# sha2017_rev0_1_dev.net
KiCad netlist of a schematic drawn in EAGLE
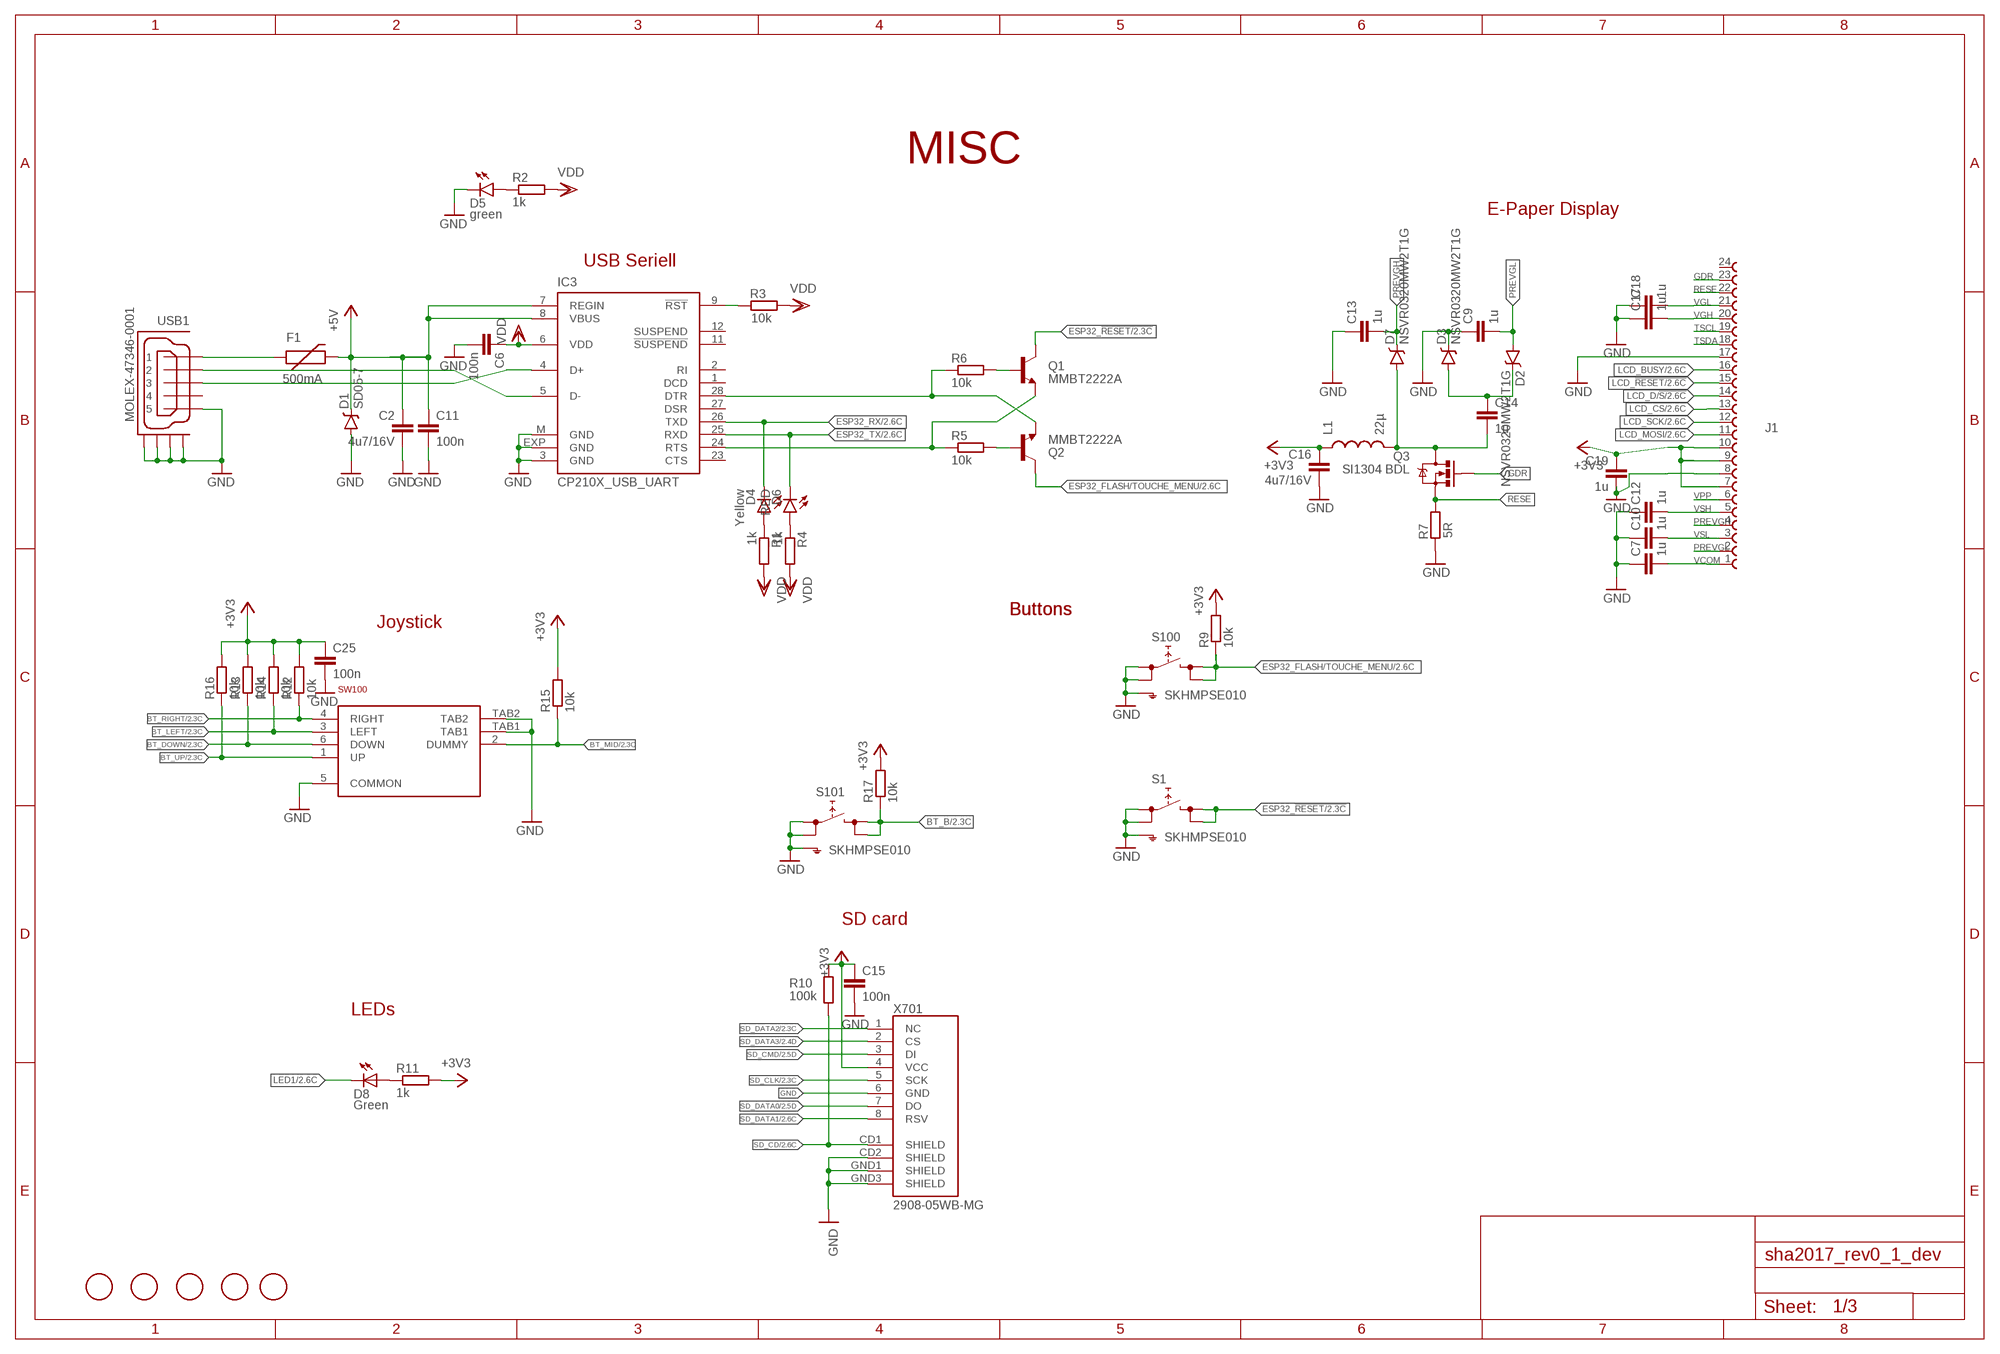
[diagram p0: schematic, sheet 1]
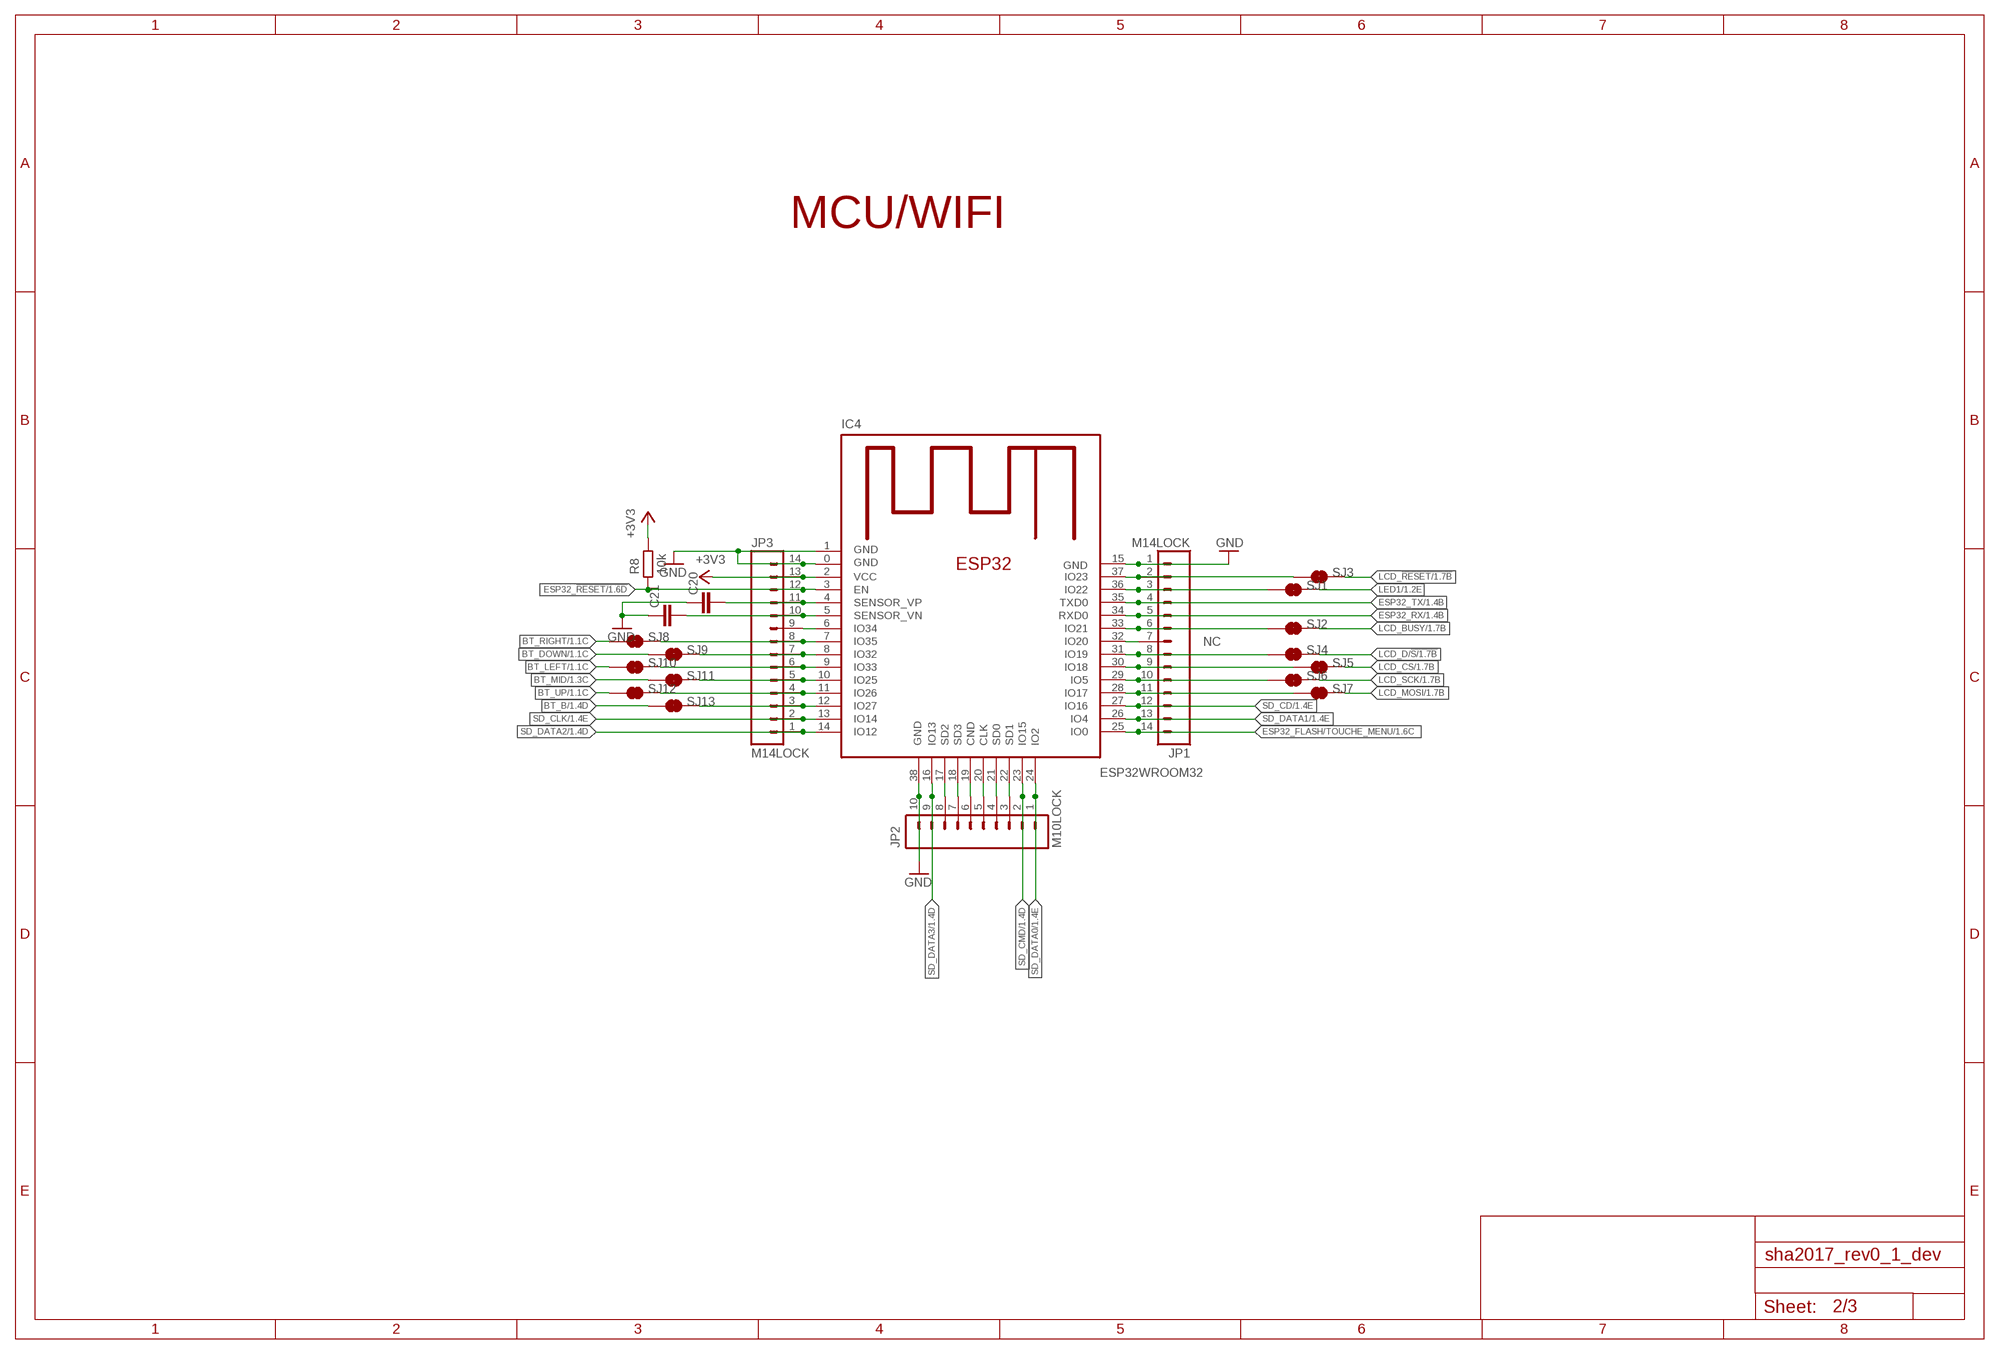
[diagram p1: schematic, sheet 2]
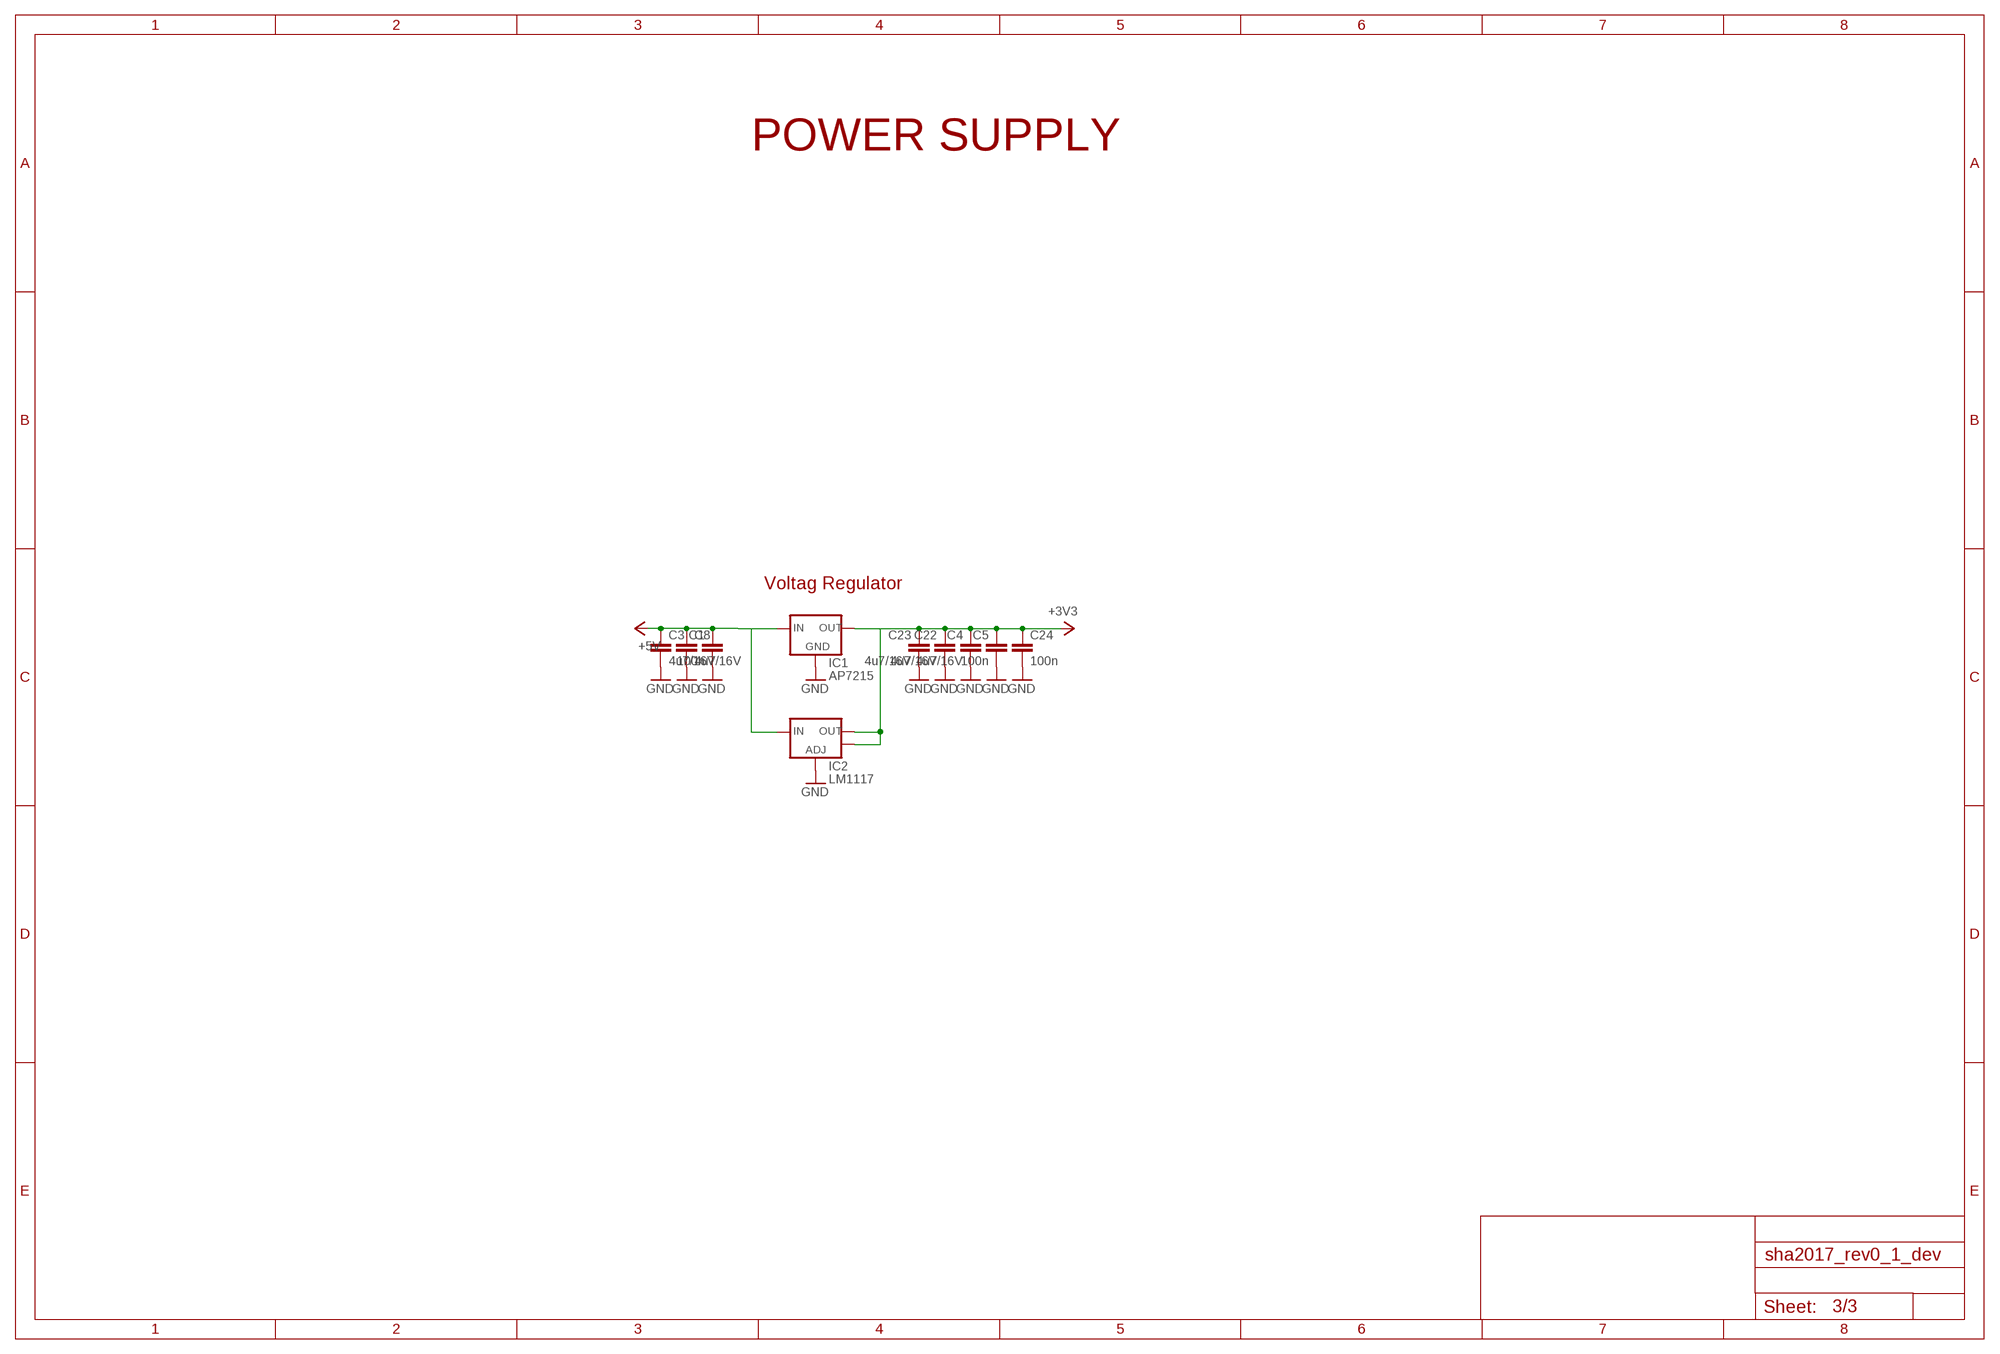
[diagram p2: schematic, sheet 3]

(export (version "E")
  (design (tool "Eeschema 10.0.6"))
  (components
    (comp (ref "C2")
      (value "4u7/16V")
      (footprint "eagle-import:C0805")
      (fields (field (name "PARTNO") "GRM21BR61C475KA88K"))
      (libsource (lib "eagle-import") (part "C-EUC0805"))
    )
    (comp (ref "C6")
      (value "100n")
      (footprint "eagle-import:C0603")
      (fields (field (name "PARTNO") "GRM188R71H104KA93D"))
      (libsource (lib "eagle-import") (part "C-EUC0603"))
    )
    (comp (ref "C7")
      (value "1u")
      (footprint "eagle-import:C0603")
      (fields (field (name "PARTNO") "GRM188R61E105KA12D"))
      (libsource (lib "eagle-import") (part "C-EUC0603"))
    )
    (comp (ref "C9")
      (value "1u")
      (footprint "eagle-import:C0603")
      (fields (field (name "PARTNO") "GRM188R61E105KA12D"))
      (libsource (lib "eagle-import") (part "C-EUC0603"))
    )
    (comp (ref "C10")
      (value "1u")
      (footprint "eagle-import:C0603")
      (fields (field (name "PARTNO") "GRM188R61E105KA12D"))
      (libsource (lib "eagle-import") (part "C-EUC0603"))
    )
    (comp (ref "C11")
      (value "100n")
      (footprint "eagle-import:C0603")
      (fields (field (name "PARTNO") "GRM188R71H104KA93D"))
      (libsource (lib "eagle-import") (part "C-EUC0603"))
    )
    (comp (ref "C12")
      (value "1u")
      (footprint "eagle-import:C0603")
      (fields (field (name "PARTNO") "GRM188R61E105KA12D"))
      (libsource (lib "eagle-import") (part "C-EUC0603"))
    )
    (comp (ref "C13")
      (value "1u")
      (footprint "eagle-import:C0603")
      (fields (field (name "PARTNO") "GRM188R61E105KA12D"))
      (libsource (lib "eagle-import") (part "C-EUC0603"))
    )
    (comp (ref "C14")
      (value "1u")
      (footprint "eagle-import:C0603")
      (fields (field (name "PARTNO") "GRM188R61E105KA12D"))
      (libsource (lib "eagle-import") (part "C-EUC0603"))
    )
    (comp (ref "C15")
      (value "100n")
      (footprint "eagle-import:C0603")
      (fields (field (name "PARTNO") "GRM188R71H104KA93D"))
      (libsource (lib "eagle-import") (part "C-EUC0603"))
    )
    (comp (ref "C16")
      (value "4u7/16V")
      (footprint "eagle-import:C0805")
      (fields (field (name "PARTNO") "GRM21BR61C475KA88K"))
      (libsource (lib "eagle-import") (part "C-EUC0805"))
    )
    (comp (ref "C17")
      (value "1u")
      (footprint "eagle-import:C0603")
      (fields (field (name "PARTNO") "GRM188R61E105KA12D"))
      (libsource (lib "eagle-import") (part "C-EUC0603"))
    )
    (comp (ref "C18")
      (value "1u")
      (footprint "eagle-import:C0603")
      (fields (field (name "PARTNO") "GRM188R61E105KA12D"))
      (libsource (lib "eagle-import") (part "C-EUC0603"))
    )
    (comp (ref "C19")
      (value "1u")
      (footprint "eagle-import:C0603")
      (fields (field (name "PARTNO") "GRM188R61E105KA12D"))
      (libsource (lib "eagle-import") (part "C-EUC0603"))
    )
    (comp (ref "C25")
      (value "100n")
      (footprint "eagle-import:C0603")
      (fields (field (name "PARTNO") "GRM188R71H104KA93D"))
      (libsource (lib "eagle-import") (part "C-EUC0603"))
    )
    (comp (ref "D1")
      (value "SD05-7")
      (footprint "eagle-import:SOD-323")
      (fields (field (name "PARTNO") "PMEG4005EJ,115"))
      (libsource (lib "eagle-import") (part "DIODE-SCHOTTKY-PMEG4005EJ"))
    )
    (comp (ref "D2")
      (value "NSVR0320MW2T1G")
      (footprint "eagle-import:SOD-323")
      (fields (field (name "PARTNO") "BAT20JFILM"))
      (libsource (lib "eagle-import") (part "BAT20JFILM"))
    )
    (comp (ref "D3")
      (value "NSVR0320MW2T1G")
      (footprint "eagle-import:SOD-323")
      (fields (field (name "PARTNO") "BAT20JFILM"))
      (libsource (lib "eagle-import") (part "BAT20JFILM"))
    )
    (comp (ref "D4")
      (value "Yellow")
      (footprint "eagle-import:LED-0603")
      (libsource (lib "eagle-import") (part "LED0603"))
    )
    (comp (ref "D5")
      (value "green")
      (footprint "eagle-import:LED-0603")
      (libsource (lib "eagle-import") (part "LED0603"))
    )
    (comp (ref "D6")
      (value "RED")
      (footprint "eagle-import:LED-0603")
      (libsource (lib "eagle-import") (part "LED0603"))
    )
    (comp (ref "D7")
      (value "NSVR0320MW2T1G")
      (footprint "eagle-import:SOD-323")
      (fields (field (name "PARTNO") "BAT20JFILM"))
      (libsource (lib "eagle-import") (part "BAT20JFILM"))
    )
    (comp (ref "D8")
      (value "Green")
      (footprint "eagle-import:SML1206")
      (fields (field (name "PARTNO") "156120VS75300"))
      (libsource (lib "eagle-import") (part "LEDSML1206"))
    )
    (comp (ref "F1")
      (value "500mA")
      (footprint "eagle-import:PTC-1206")
      (fields (field (name "PARTNO") "0ZCJ0025FF2E"))
      (libsource (lib "eagle-import") (part "PTCSMD"))
    )
    (comp (ref "FD1")
      (value "FIDUCIAL")
      (footprint "eagle-import:FIDUCIAL_1MM")
      (libsource (lib "eagle-import") (part "FIDUCIAL"))
    )
    (comp (ref "FD2")
      (value "FIDUCIAL")
      (footprint "eagle-import:FIDUCIAL_1MM")
      (libsource (lib "eagle-import") (part "FIDUCIAL"))
    )
    (comp (ref "FD3")
      (value "FIDUCIAL")
      (footprint "eagle-import:FIDUCIAL_1MM")
      (libsource (lib "eagle-import") (part "FIDUCIAL"))
    )
    (comp (ref "FD4")
      (value "FIDUCIAL")
      (footprint "eagle-import:FIDUCIAL_1MM")
      (libsource (lib "eagle-import") (part "FIDUCIAL"))
    )
    (comp (ref "FD5")
      (value "FIDUCIAL")
      (footprint "eagle-import:FIDUCIAL_1MM")
      (libsource (lib "eagle-import") (part "FIDUCIAL"))
    )
    (comp (ref "IC3")
      (value "CP210X_USB_UART")
      (footprint "eagle-import:MLP28")
      (fields (field (name "PARTNO") "CP2102-GMR"))
      (libsource (lib "eagle-import") (part "CP210X_USB_UART"))
    )
    (comp (ref "J1")
      (value "68712414022")
      (footprint "eagle-import:68712414022")
      (libsource (lib "eagle-import") (part "68712414022"))
    )
    (comp (ref "L1")
      (value "22µ")
      (footprint "eagle-import:1210")
      (fields (field (name "PARTNO") "NLCV32T-220K-EF"))
      (libsource (lib "eagle-import") (part "INDUCTOR1210"))
    )
    (comp (ref "Q1")
      (value "MMBT2222A")
      (footprint "eagle-import:SOT23-3")
      (fields (field (name "PARTNO") "BC817-25,215"))
      (libsource (lib "eagle-import") (part "TRANSISTOR_NPNMMBT2222A"))
    )
    (comp (ref "Q2")
      (value "MMBT2222A")
      (footprint "eagle-import:SOT23-3")
      (fields (field (name "PARTNO") "BC817-25,215"))
      (libsource (lib "eagle-import") (part "TRANSISTOR_NPNMMBT2222A"))
    )
    (comp (ref "Q3")
      (value "SI1304 BDL")
      (footprint "eagle-import:SOT323")
      (fields (field (name "PARTNO") "SI1308EDL-T1-GE3"))
      (libsource (lib "eagle-import") (part "MOSFET-NCHANNEL2N7002PW"))
    )
    (comp (ref "R1")
      (value "1k")
      (footprint "eagle-import:R0603")
      (fields (field (name "PARTNO") "ERJ-3GEYJ102V"))
      (libsource (lib "eagle-import") (part "R-EU_R0603"))
    )
    (comp (ref "R2")
      (value "1k")
      (footprint "eagle-import:R0603")
      (fields (field (name "PARTNO") "ERJ-3GEYJ102V"))
      (libsource (lib "eagle-import") (part "R-EU_R0603"))
    )
    (comp (ref "R3")
      (value "10k")
      (footprint "eagle-import:R0603")
      (fields (field (name "PARTNO") "ERJ-3GEYJ103V"))
      (libsource (lib "eagle-import") (part "R-EU_R0603"))
    )
    (comp (ref "R4")
      (value "1k")
      (footprint "eagle-import:R0603")
      (fields (field (name "PARTNO") "ERJ-3GEYJ102V"))
      (libsource (lib "eagle-import") (part "R-EU_R0603"))
    )
    (comp (ref "R5")
      (value "10k")
      (footprint "eagle-import:R0603")
      (fields (field (name "PARTNO") "ERJ-3GEYJ103V"))
      (libsource (lib "eagle-import") (part "R-EU_R0603"))
    )
    (comp (ref "R6")
      (value "10k")
      (footprint "eagle-import:R0603")
      (fields (field (name "PARTNO") "ERJ-3GEYJ103V"))
      (libsource (lib "eagle-import") (part "R-EU_R0603"))
    )
    (comp (ref "R7")
      (value "5R")
      (footprint "eagle-import:R0603-DASHES")
      (fields (field (name "PARTNO") "ERJ-3GEYJ5R1V"))
      (libsource (lib "eagle-import") (part "R0603-DASHES"))
    )
    (comp (ref "R9")
      (value "10k")
      (footprint "eagle-import:R0603")
      (fields (field (name "PARTNO") "ERJ-3GEYJ103V"))
      (libsource (lib "eagle-import") (part "R-EU_R0603"))
    )
    (comp (ref "R10")
      (value "100k")
      (footprint "eagle-import:R0603")
      (fields (field (name "PARTNO") "CRCW0603100KFKEA"))
      (libsource (lib "eagle-import") (part "R-EU_R0603"))
    )
    (comp (ref "R11")
      (value "1k")
      (footprint "eagle-import:R0603")
      (fields (field (name "PARTNO") "ERJ-3GEYJ102V"))
      (libsource (lib "eagle-import") (part "R-EU_R0603"))
    )
    (comp (ref "R12")
      (value "10k")
      (footprint "eagle-import:R0603")
      (fields (field (name "PARTNO") "ERJ-3GEYJ103V"))
      (libsource (lib "eagle-import") (part "R-EU_R0603"))
    )
    (comp (ref "R13")
      (value "10k")
      (footprint "eagle-import:R0603")
      (fields (field (name "PARTNO") "ERJ-3GEYJ103V"))
      (libsource (lib "eagle-import") (part "R-EU_R0603"))
    )
    (comp (ref "R14")
      (value "10k")
      (footprint "eagle-import:R0603")
      (fields (field (name "PARTNO") "ERJ-3GEYJ103V"))
      (libsource (lib "eagle-import") (part "R-EU_R0603"))
    )
    (comp (ref "R15")
      (value "10k")
      (footprint "eagle-import:R0603")
      (fields (field (name "PARTNO") "ERJ-3GEYJ103V"))
      (libsource (lib "eagle-import") (part "R-EU_R0603"))
    )
    (comp (ref "R16")
      (value "10k")
      (footprint "eagle-import:R0603")
      (fields (field (name "PARTNO") "ERJ-3GEYJ103V"))
      (libsource (lib "eagle-import") (part "R-EU_R0603"))
    )
    (comp (ref "R17")
      (value "10k")
      (footprint "eagle-import:R0603")
      (fields (field (name "PARTNO") "ERJ-3GEYJ103V"))
      (libsource (lib "eagle-import") (part "R-EU_R0603"))
    )
    (comp (ref "S1")
      (value "SKHMPSE010")
      (footprint "eagle-import:SKHMPXE010")
      (fields (field (name "PARTNO") "SKHMQME010"))
      (libsource (lib "eagle-import") (part "SKHMPE010S"))
    )
    (comp (ref "S100")
      (value "SKHMPSE010")
      (footprint "eagle-import:SKHMPXE010")
      (fields (field (name "PARTNO") "SKHMQME010"))
      (libsource (lib "eagle-import") (part "SKHMPE010S"))
    )
    (comp (ref "S101")
      (value "SKHMPSE010")
      (footprint "eagle-import:SKHMPXE010")
      (fields (field (name "PARTNO") "SKHMQME010"))
      (libsource (lib "eagle-import") (part "SKHMPE010S"))
    )
    (comp (ref "SW100")
      (value "MCMT5-F-V")
      (footprint "eagle-import:MCMT5-F-V")
      (fields (field (name "PARTNO") "SKRHAAE010"))
      (libsource (lib "eagle-import") (part "MCMT5-F-V"))
    )
    (comp (ref "USB1")
      (value "MOLEX-47346-0001")
      (footprint "eagle-import:MOLEX-47364-0001")
      (fields (field (name "PARTNO") "10118194-0001LF"))
      (libsource (lib "eagle-import") (part "MOLEX-47346-0001"))
    )
    (comp (ref "X701")
      (value "2908-05WB-MG")
      (footprint "eagle-import:MICRO-SD-SOCKET-PP")
      (libsource (lib "eagle-import") (part "2908-05WB-MG"))
    )
    (comp (ref "C1")
      (value "100n")
      (footprint "eagle-import:C0603")
      (fields (field (name "PARTNO") "GRM188R71H104KA93D"))
      (libsource (lib "eagle-import") (part "C-EUC0603"))
    )
    (comp (ref "C3")
      (value "4u7/16V")
      (footprint "eagle-import:C0805")
      (fields (field (name "PARTNO") "GRM21BR61C475KA88K"))
      (libsource (lib "eagle-import") (part "C-EUC0805"))
    )
    (comp (ref "C4")
      (value "4u7/16V")
      (footprint "eagle-import:C0805")
      (fields (field (name "PARTNO") "GRM21BR61C475KA88K"))
      (libsource (lib "eagle-import") (part "C-EUC0805"))
    )
    (comp (ref "C5")
      (value "100n")
      (footprint "eagle-import:C0603")
      (fields (field (name "PARTNO") "GRM188R71H104KA93D"))
      (libsource (lib "eagle-import") (part "C-EUC0603"))
    )
    (comp (ref "C8")
      (value "4u7/16V")
      (footprint "eagle-import:C0805")
      (fields (field (name "PARTNO") "GRM21BR61C475KA88K"))
      (libsource (lib "eagle-import") (part "C-EUC0805"))
    )
    (comp (ref "C22")
      (value "4u7/16V")
      (footprint "eagle-import:C0805")
      (fields (field (name "PARTNO") "GRM21BR61C475KA88K"))
      (libsource (lib "eagle-import") (part "C-EUC0805"))
    )
    (comp (ref "C23")
      (value "4u7/16V")
      (footprint "eagle-import:C0805")
      (fields (field (name "PARTNO") "GRM21BR61C475KA88K"))
      (libsource (lib "eagle-import") (part "C-EUC0805"))
    )
    (comp (ref "C24")
      (value "100n")
      (footprint "eagle-import:C0603")
      (fields (field (name "PARTNO") "GRM188R71H104KA93D"))
      (libsource (lib "eagle-import") (part "C-EUC0603"))
    )
    (comp (ref "IC1")
      (value "AP7215")
      (footprint "eagle-import:SOT89")
      (fields (field (name "PARTNO") "AP7215-33YG-13"))
      (libsource (lib "eagle-import") (part "AP7215"))
    )
    (comp (ref "IC2")
      (value "LM1117")
      (footprint "eagle-import:SOT223")
      (fields (field (name "PARTNO") "LM1117MPX-3.3/NOPB"))
      (libsource (lib "eagle-import") (part "V_REG_LM1117SOT223"))
    )
    (comp (ref "C20")
      (value "C-EUC0603")
      (footprint "eagle-import:C0603")
      (libsource (lib "eagle-import") (part "C-EUC0603"))
    )
    (comp (ref "C21")
      (value "C-EUC0603")
      (footprint "eagle-import:C0603")
      (libsource (lib "eagle-import") (part "C-EUC0603"))
    )
    (comp (ref "IC4")
      (value "ESP32WROOM32")
      (footprint "eagle-import:ESP32MOD")
      (libsource (lib "eagle-import") (part "ESP32WROOM32"))
    )
    (comp (ref "JP1")
      (value "M14LOCK")
      (footprint "eagle-import:1X14_LOCK")
      (libsource (lib "eagle-import") (part "M14LOCK"))
    )
    (comp (ref "JP2")
      (value "M10LOCK")
      (footprint "eagle-import:1X10_LOCK")
      (libsource (lib "eagle-import") (part "M10LOCK"))
    )
    (comp (ref "JP3")
      (value "M14LOCK")
      (footprint "eagle-import:1X14_LOCK")
      (libsource (lib "eagle-import") (part "M14LOCK"))
    )
    (comp (ref "R8")
      (value "10k")
      (footprint "eagle-import:R0603")
      (fields (field (name "PARTNO") "ERJ-3GEYJ103V"))
      (libsource (lib "eagle-import") (part "R-EU_R0603"))
    )
    (comp (ref "SJ1")
      (value "JUMPER-PAD-2-NC_BY_TRACE")
      (footprint "eagle-import:PAD-JUMPER-2-NC_BY_TRACE_YES_SILK")
      (libsource (lib "eagle-import") (part "JUMPER-PAD-2-NC_BY_TRACE"))
    )
    (comp (ref "SJ2")
      (value "JUMPER-PAD-2-NC_BY_TRACE")
      (footprint "eagle-import:PAD-JUMPER-2-NC_BY_TRACE_YES_SILK")
      (libsource (lib "eagle-import") (part "JUMPER-PAD-2-NC_BY_TRACE"))
    )
    (comp (ref "SJ3")
      (value "JUMPER-PAD-2-NC_BY_TRACE")
      (footprint "eagle-import:PAD-JUMPER-2-NC_BY_TRACE_YES_SILK")
      (libsource (lib "eagle-import") (part "JUMPER-PAD-2-NC_BY_TRACE"))
    )
    (comp (ref "SJ4")
      (value "JUMPER-PAD-2-NC_BY_TRACE")
      (footprint "eagle-import:PAD-JUMPER-2-NC_BY_TRACE_YES_SILK")
      (libsource (lib "eagle-import") (part "JUMPER-PAD-2-NC_BY_TRACE"))
    )
    (comp (ref "SJ5")
      (value "JUMPER-PAD-2-NC_BY_TRACE")
      (footprint "eagle-import:PAD-JUMPER-2-NC_BY_TRACE_YES_SILK")
      (libsource (lib "eagle-import") (part "JUMPER-PAD-2-NC_BY_TRACE"))
    )
    (comp (ref "SJ6")
      (value "JUMPER-PAD-2-NC_BY_TRACE")
      (footprint "eagle-import:PAD-JUMPER-2-NC_BY_TRACE_YES_SILK")
      (libsource (lib "eagle-import") (part "JUMPER-PAD-2-NC_BY_TRACE"))
    )
    (comp (ref "SJ7")
      (value "JUMPER-PAD-2-NC_BY_TRACE")
      (footprint "eagle-import:PAD-JUMPER-2-NC_BY_TRACE_YES_SILK")
      (libsource (lib "eagle-import") (part "JUMPER-PAD-2-NC_BY_TRACE"))
    )
    (comp (ref "SJ8")
      (value "JUMPER-PAD-2-NC_BY_TRACE")
      (footprint "eagle-import:PAD-JUMPER-2-NC_BY_TRACE_YES_SILK")
      (libsource (lib "eagle-import") (part "JUMPER-PAD-2-NC_BY_TRACE"))
    )
    (comp (ref "SJ9")
      (value "JUMPER-PAD-2-NC_BY_TRACE")
      (footprint "eagle-import:PAD-JUMPER-2-NC_BY_TRACE_YES_SILK")
      (libsource (lib "eagle-import") (part "JUMPER-PAD-2-NC_BY_TRACE"))
    )
    (comp (ref "SJ10")
      (value "JUMPER-PAD-2-NC_BY_TRACE")
      (footprint "eagle-import:PAD-JUMPER-2-NC_BY_TRACE_YES_SILK")
      (libsource (lib "eagle-import") (part "JUMPER-PAD-2-NC_BY_TRACE"))
    )
    (comp (ref "SJ11")
      (value "JUMPER-PAD-2-NC_BY_TRACE")
      (footprint "eagle-import:PAD-JUMPER-2-NC_BY_TRACE_YES_SILK")
      (libsource (lib "eagle-import") (part "JUMPER-PAD-2-NC_BY_TRACE"))
    )
    (comp (ref "SJ12")
      (value "JUMPER-PAD-2-NC_BY_TRACE")
      (footprint "eagle-import:PAD-JUMPER-2-NC_BY_TRACE_YES_SILK")
      (libsource (lib "eagle-import") (part "JUMPER-PAD-2-NC_BY_TRACE"))
    )
    (comp (ref "SJ13")
      (value "JUMPER-PAD-2-NC_BY_TRACE")
      (footprint "eagle-import:PAD-JUMPER-2-NC_BY_TRACE_YES_SILK")
      (libsource (lib "eagle-import") (part "JUMPER-PAD-2-NC_BY_TRACE"))
    )
  )
  (nets
    (net (code "1") (name "+3V3") (class "Default")
      (node (ref "C15") (pin "1") (pinfunction "1_1") (pintype "passive"))
      (node (ref "C16") (pin "1") (pinfunction "1_1") (pintype "passive"))
      (node (ref "C19") (pin "1") (pinfunction "1_1") (pintype "passive"))
      (node (ref "C22") (pin "1") (pinfunction "1_1") (pintype "passive"))
      (node (ref "C23") (pin "1") (pinfunction "1_1") (pintype "passive"))
      (node (ref "C24") (pin "1") (pinfunction "1_1") (pintype "passive"))
      (node (ref "C25") (pin "1") (pinfunction "1_1") (pintype "passive"))
      (node (ref "C4") (pin "1") (pinfunction "1_1") (pintype "passive"))
      (node (ref "C5") (pin "1") (pinfunction "1_1") (pintype "passive"))
      (node (ref "IC1") (pin "3") (pinfunction "OUT_3") (pintype "passive"))
      (node (ref "IC2") (pin "2") (pinfunction "OUT_2") (pintype "output"))
      (node (ref "IC2") (pin "4") (pinfunction "OUT_4") (pintype "output"))
      (node (ref "IC4") (pin "2") (pinfunction "VCC_2") (pintype "power_in"))
      (node (ref "J1") (pin "10") (pinfunction "10_10") (pintype "passive"))
      (node (ref "J1") (pin "7") (pinfunction "7_7") (pintype "passive"))
      (node (ref "J1") (pin "9") (pinfunction "9_9") (pintype "passive"))
      (node (ref "JP3") (pin "13") (pinfunction "13_13") (pintype "passive"))
      (node (ref "L1") (pin "1") (pinfunction "1_1") (pintype "passive"))
      (node (ref "R10") (pin "1") (pinfunction "1_1") (pintype "passive"))
      (node (ref "R11") (pin "2") (pinfunction "2_2") (pintype "passive"))
      (node (ref "R12") (pin "2") (pinfunction "2_2") (pintype "passive"))
      (node (ref "R13") (pin "2") (pinfunction "2_2") (pintype "passive"))
      (node (ref "R14") (pin "2") (pinfunction "2_2") (pintype "passive"))
      (node (ref "R15") (pin "2") (pinfunction "2_2") (pintype "passive"))
      (node (ref "R16") (pin "2") (pinfunction "2_2") (pintype "passive"))
      (node (ref "R17") (pin "2") (pinfunction "2_2") (pintype "passive"))
      (node (ref "R8") (pin "1") (pinfunction "1_1") (pintype "passive"))
      (node (ref "R9") (pin "2") (pinfunction "2_2") (pintype "passive"))
      (node (ref "X701") (pin "4") (pinfunction "VCC_4") (pintype "bidirectional"))
    )
    (net (code "2") (name "+5V") (class "Default")
      (node (ref "C1") (pin "1") (pinfunction "1_1") (pintype "passive"))
      (node (ref "C11") (pin "1") (pinfunction "1_1") (pintype "passive"))
      (node (ref "C2") (pin "1") (pinfunction "1_1") (pintype "passive"))
      (node (ref "C3") (pin "1") (pinfunction "1_1") (pintype "passive"))
      (node (ref "C8") (pin "1") (pinfunction "1_1") (pintype "passive"))
      (node (ref "D1") (pin "C") (pinfunction "C_C") (pintype "passive"))
      (node (ref "F1") (pin "2") (pinfunction "2_2") (pintype "bidirectional"))
      (node (ref "IC1") (pin "2") (pinfunction "IN_2") (pintype "input"))
      (node (ref "IC1") (pin "2@") (pinfunction "IN_2@") (pintype "input"))
      (node (ref "IC2") (pin "3") (pinfunction "IN_3") (pintype "input"))
      (node (ref "IC3") (pin "7") (pinfunction "REGIN_7") (pintype "passive"))
      (node (ref "IC3") (pin "8") (pinfunction "VBUS_8") (pintype "input"))
    )
    (net (code "3") (name "BT_B") (class "Default")
      (node (ref "R17") (pin "1") (pinfunction "1_1") (pintype "passive"))
      (node (ref "S101") (pin "3") (pinfunction "2.1_3") (pintype "passive"))
      (node (ref "S101") (pin "4") (pinfunction "2.2_4") (pintype "passive"))
      (node (ref "SJ13") (pin "1") (pinfunction "1_1") (pintype "passive"))
    )
    (net (code "4") (name "BT_DOWN") (class "Default")
      (node (ref "R13") (pin "1") (pinfunction "1_1") (pintype "passive"))
      (node (ref "SJ9") (pin "1") (pinfunction "1_1") (pintype "passive"))
      (node (ref "SW100") (pin "6") (pinfunction "DOWN_6") (pintype "bidirectional"))
    )
    (net (code "5") (name "BT_LEFT") (class "Default")
      (node (ref "R14") (pin "1") (pinfunction "1_1") (pintype "passive"))
      (node (ref "SJ10") (pin "1") (pinfunction "1_1") (pintype "passive"))
      (node (ref "SW100") (pin "3") (pinfunction "LEFT_3") (pintype "bidirectional"))
    )
    (net (code "6") (name "BT_MID") (class "Default")
      (node (ref "R15") (pin "1") (pinfunction "1_1") (pintype "passive"))
      (node (ref "SJ11") (pin "1") (pinfunction "1_1") (pintype "passive"))
      (node (ref "SW100") (pin "2") (pinfunction "DUMMY_2") (pintype "bidirectional"))
    )
    (net (code "7") (name "BT_RIGHT") (class "Default")
      (node (ref "R12") (pin "1") (pinfunction "1_1") (pintype "passive"))
      (node (ref "SJ8") (pin "1") (pinfunction "1_1") (pintype "passive"))
      (node (ref "SW100") (pin "4") (pinfunction "RIGHT_4") (pintype "bidirectional"))
    )
    (net (code "8") (name "BT_UP") (class "Default")
      (node (ref "R16") (pin "1") (pinfunction "1_1") (pintype "passive"))
      (node (ref "SJ12") (pin "1") (pinfunction "1_1") (pintype "passive"))
      (node (ref "SW100") (pin "1") (pinfunction "UP_1") (pintype "bidirectional"))
    )
    (net (code "9") (name "ESP32_FLASH{slash}TOUCHE_MENU") (class "Default")
      (node (ref "IC4") (pin "25") (pinfunction "IO0_25") (pintype "bidirectional"))
      (node (ref "JP1") (pin "14") (pinfunction "14_14") (pintype "passive"))
      (node (ref "Q2") (pin "3") (pinfunction "C_3") (pintype "passive"))
      (node (ref "R9") (pin "1") (pinfunction "1_1") (pintype "passive"))
      (node (ref "S100") (pin "3") (pinfunction "2.1_3") (pintype "passive"))
      (node (ref "S100") (pin "4") (pinfunction "2.2_4") (pintype "passive"))
    )
    (net (code "10") (name "ESP32_RX") (class "Default")
      (node (ref "D4") (pin "C") (pinfunction "C_C") (pintype "passive"))
      (node (ref "IC3") (pin "26") (pinfunction "TXD_26") (pintype "output"))
      (node (ref "IC4") (pin "34") (pinfunction "RXD0_34") (pintype "bidirectional"))
      (node (ref "JP1") (pin "5") (pinfunction "5_5") (pintype "passive"))
    )
    (net (code "11") (name "ESP32_TX") (class "Default")
      (node (ref "D6") (pin "C") (pinfunction "C_C") (pintype "passive"))
      (node (ref "IC3") (pin "25") (pinfunction "RXD_25") (pintype "input"))
      (node (ref "IC4") (pin "35") (pinfunction "TXD0_35") (pintype "bidirectional"))
      (node (ref "JP1") (pin "4") (pinfunction "4_4") (pintype "passive"))
    )
    (net (code "12") (name "ESP32_~{RESET}") (class "Default")
      (node (ref "IC4") (pin "3") (pinfunction "EN_3") (pintype "bidirectional"))
      (node (ref "JP3") (pin "12") (pinfunction "12_12") (pintype "passive"))
      (node (ref "Q1") (pin "3") (pinfunction "C_3") (pintype "passive"))
      (node (ref "R8") (pin "2") (pinfunction "2_2") (pintype "passive"))
      (node (ref "S1") (pin "3") (pinfunction "2.1_3") (pintype "passive"))
      (node (ref "S1") (pin "4") (pinfunction "2.2_4") (pintype "passive"))
    )
    (net (code "13") (name "GDR") (class "Default")
      (node (ref "J1") (pin "23") (pinfunction "23_23") (pintype "passive"))
      (node (ref "Q3") (pin "1") (pinfunction "G_1") (pintype "passive"))
    )
    (net (code "14") (name "GND") (class "Default")
      (node (ref "C1") (pin "2") (pinfunction "2_2") (pintype "passive"))
      (node (ref "C10") (pin "1") (pinfunction "1_1") (pintype "passive"))
      (node (ref "C11") (pin "2") (pinfunction "2_2") (pintype "passive"))
      (node (ref "C12") (pin "1") (pinfunction "1_1") (pintype "passive"))
      (node (ref "C13") (pin "1") (pinfunction "1_1") (pintype "passive"))
      (node (ref "C15") (pin "2") (pinfunction "2_2") (pintype "passive"))
      (node (ref "C16") (pin "2") (pinfunction "2_2") (pintype "passive"))
      (node (ref "C17") (pin "1") (pinfunction "1_1") (pintype "passive"))
      (node (ref "C18") (pin "1") (pinfunction "1_1") (pintype "passive"))
      (node (ref "C19") (pin "2") (pinfunction "2_2") (pintype "passive"))
      (node (ref "C2") (pin "2") (pinfunction "2_2") (pintype "passive"))
      (node (ref "C20") (pin "1") (pinfunction "1_1") (pintype "passive"))
      (node (ref "C21") (pin "1") (pinfunction "1_1") (pintype "passive"))
      (node (ref "C22") (pin "2") (pinfunction "2_2") (pintype "passive"))
      (node (ref "C23") (pin "2") (pinfunction "2_2") (pintype "passive"))
      (node (ref "C24") (pin "2") (pinfunction "2_2") (pintype "passive"))
      (node (ref "C25") (pin "2") (pinfunction "2_2") (pintype "passive"))
      (node (ref "C3") (pin "2") (pinfunction "2_2") (pintype "passive"))
      (node (ref "C4") (pin "2") (pinfunction "2_2") (pintype "passive"))
      (node (ref "C5") (pin "2") (pinfunction "2_2") (pintype "passive"))
      (node (ref "C6") (pin "2") (pinfunction "2_2") (pintype "passive"))
      (node (ref "C7") (pin "1") (pinfunction "1_1") (pintype "passive"))
      (node (ref "C8") (pin "2") (pinfunction "2_2") (pintype "passive"))
      (node (ref "C9") (pin "1") (pinfunction "1_1") (pintype "passive"))
      (node (ref "D1") (pin "A") (pinfunction "A_A") (pintype "passive"))
      (node (ref "D3") (pin "C") (pinfunction "C_C") (pintype "passive"))
      (node (ref "D5") (pin "C") (pinfunction "C_C") (pintype "passive"))
      (node (ref "IC1") (pin "1") (pinfunction "GND_1") (pintype "input"))
      (node (ref "IC2") (pin "1") (pinfunction "ADJ_1") (pintype "input"))
      (node (ref "IC3") (pin "3") (pinfunction "GND_3") (pintype "power_in"))
      (node (ref "IC3") (pin "EXP") (pinfunction "GND_EXP") (pintype "power_in"))
      (node (ref "IC3") (pin "M") (pinfunction "GND_M") (pintype "power_in"))
      (node (ref "IC4") (pin "0") (pinfunction "GND_0") (pintype "power_in"))
      (node (ref "IC4") (pin "1") (pinfunction "GND_1") (pintype "power_in"))
      (node (ref "IC4") (pin "15") (pinfunction "GND_15") (pintype "power_in"))
      (node (ref "IC4") (pin "38") (pinfunction "GND_38") (pintype "power_in"))
      (node (ref "J1") (pin "17") (pinfunction "17_17") (pintype "passive"))
      (node (ref "J1") (pin "8") (pinfunction "8_8") (pintype "passive"))
      (node (ref "JP1") (pin "1") (pinfunction "1_1") (pintype "passive"))
      (node (ref "JP2") (pin "10") (pinfunction "10_10") (pintype "passive"))
      (node (ref "JP3") (pin "14") (pinfunction "14_14") (pintype "passive"))
      (node (ref "R7") (pin "2") (pinfunction "2_2") (pintype "passive"))
      (node (ref "S1") (pin "1") (pinfunction "1.1_1") (pintype "passive"))
      (node (ref "S1") (pin "2") (pinfunction "1.2_2") (pintype "passive"))
      (node (ref "S1") (pin "5") (pinfunction "SH_5") (pintype "passive"))
      (node (ref "S100") (pin "1") (pinfunction "1.1_1") (pintype "passive"))
      (node (ref "S100") (pin "2") (pinfunction "1.2_2") (pintype "passive"))
      (node (ref "S100") (pin "5") (pinfunction "SH_5") (pintype "passive"))
      (node (ref "S101") (pin "1") (pinfunction "1.1_1") (pintype "passive"))
      (node (ref "S101") (pin "2") (pinfunction "1.2_2") (pintype "passive"))
      (node (ref "S101") (pin "5") (pinfunction "SH_5") (pintype "passive"))
      (node (ref "SW100") (pin "5") (pinfunction "COMMON_5") (pintype "bidirectional"))
      (node (ref "SW100") (pin "TAB1") (pinfunction "TAB1_TAB1") (pintype "bidirectional"))
      (node (ref "SW100") (pin "TAB2") (pinfunction "TAB2_TAB2") (pintype "bidirectional"))
      (node (ref "USB1") (pin "5") (pinfunction "5_5") (pintype "input"))
      (node (ref "USB1") (pin "GND1") (pinfunction "GND1_GND1") (pintype "bidirectional"))
      (node (ref "USB1") (pin "GND2") (pinfunction "GND2_GND2") (pintype "bidirectional"))
      (node (ref "USB1") (pin "GND3") (pinfunction "GND3_GND3") (pintype "bidirectional"))
      (node (ref "USB1") (pin "GND4") (pinfunction "GND4_GND4") (pintype "bidirectional"))
      (node (ref "X701") (pin "6") (pinfunction "GND_6") (pintype "bidirectional"))
      (node (ref "X701") (pin "CD2") (pinfunction "SHIELD_CD2") (pintype "bidirectional"))
      (node (ref "X701") (pin "GND1") (pinfunction "SHIELD_GND1") (pintype "bidirectional"))
      (node (ref "X701") (pin "GND3") (pinfunction "SHIELD_GND3") (pintype "bidirectional"))
    )
    (net (code "15") (name "LCD_BUSY") (class "Default")
      (node (ref "J1") (pin "16") (pinfunction "16_16") (pintype "passive"))
      (node (ref "SJ2") (pin "2") (pinfunction "2_2") (pintype "passive"))
    )
    (net (code "16") (name "LCD_CS") (class "Default")
      (node (ref "J1") (pin "13") (pinfunction "13_13") (pintype "passive"))
      (node (ref "SJ5") (pin "2") (pinfunction "2_2") (pintype "passive"))
    )
    (net (code "17") (name "LCD_D{slash}~{S}") (class "Default")
      (node (ref "J1") (pin "14") (pinfunction "14_14") (pintype "passive"))
      (node (ref "SJ4") (pin "2") (pinfunction "2_2") (pintype "passive"))
    )
    (net (code "18") (name "LCD_MOSI") (class "Default")
      (node (ref "J1") (pin "11") (pinfunction "11_11") (pintype "passive"))
      (node (ref "SJ7") (pin "2") (pinfunction "2_2") (pintype "passive"))
    )
    (net (code "19") (name "LCD_SCK") (class "Default")
      (node (ref "J1") (pin "12") (pinfunction "12_12") (pintype "passive"))
      (node (ref "SJ6") (pin "2") (pinfunction "2_2") (pintype "passive"))
    )
    (net (code "20") (name "LCD_~{RESET}") (class "Default")
      (node (ref "J1") (pin "15") (pinfunction "15_15") (pintype "passive"))
      (node (ref "SJ3") (pin "2") (pinfunction "2_2") (pintype "passive"))
    )
    (net (code "21") (name "LED1") (class "Default")
      (node (ref "D8") (pin "C") (pinfunction "C_C") (pintype "passive"))
      (node (ref "SJ1") (pin "2") (pinfunction "2_2") (pintype "passive"))
    )
    (net (code "22") (name "Net-(C14-Pad1)") (class "Default")
      (node (ref "C14") (pin "1") (pinfunction "1_1") (pintype "passive"))
      (node (ref "D2") (pin "C") (pinfunction "C_C") (pintype "passive"))
      (node (ref "D3") (pin "A") (pinfunction "A_A") (pintype "passive"))
    )
    (net (code "23") (name "Net-(D4-PadA)") (class "Default")
      (node (ref "D4") (pin "A") (pinfunction "A_A") (pintype "passive"))
      (node (ref "R1") (pin "1") (pinfunction "1_1") (pintype "passive"))
    )
    (net (code "24") (name "Net-(D5-PadA)") (class "Default")
      (node (ref "D5") (pin "A") (pinfunction "A_A") (pintype "passive"))
      (node (ref "R2") (pin "1") (pinfunction "1_1") (pintype "passive"))
    )
    (net (code "25") (name "Net-(D6-PadA)") (class "Default")
      (node (ref "D6") (pin "A") (pinfunction "A_A") (pintype "passive"))
      (node (ref "R4") (pin "1") (pinfunction "1_1") (pintype "passive"))
    )
    (net (code "26") (name "Net-(D8-PadA)") (class "Default")
      (node (ref "D8") (pin "A") (pinfunction "A_A") (pintype "passive"))
      (node (ref "R11") (pin "1") (pinfunction "1_1") (pintype "passive"))
    )
    (net (code "27") (name "Net-(F1-Pad1)") (class "Default")
      (node (ref "F1") (pin "1") (pinfunction "1_1") (pintype "bidirectional"))
      (node (ref "USB1") (pin "1") (pinfunction "1_1") (pintype "input"))
    )
    (net (code "28") (name "Net-(IC3-D+)") (class "Default")
      (node (ref "IC3") (pin "4") (pinfunction "D+_4") (pintype "bidirectional"))
      (node (ref "USB1") (pin "3") (pinfunction "3_3") (pintype "input"))
    )
    (net (code "29") (name "Net-(IC3-D-)") (class "Default")
      (node (ref "IC3") (pin "5") (pinfunction "D-_5") (pintype "bidirectional"))
      (node (ref "USB1") (pin "2") (pinfunction "2_2") (pintype "input"))
    )
    (net (code "30") (name "Net-(IC3-DTR)") (class "Default")
      (node (ref "IC3") (pin "28") (pinfunction "DTR_28") (pintype "output"))
      (node (ref "Q2") (pin "2") (pinfunction "E_2") (pintype "passive"))
      (node (ref "R6") (pin "1") (pinfunction "1_1") (pintype "passive"))
    )
    (net (code "31") (name "Net-(IC3-RTS)") (class "Default")
      (node (ref "IC3") (pin "24") (pinfunction "RTS_24") (pintype "output"))
      (node (ref "Q1") (pin "2") (pinfunction "E_2") (pintype "passive"))
      (node (ref "R5") (pin "1") (pinfunction "1_1") (pintype "passive"))
    )
    (net (code "32") (name "Net-(IC3-~{RST})") (class "Default")
      (node (ref "IC3") (pin "9") (pinfunction "~{RST}_9") (pintype "bidirectional"))
      (node (ref "R3") (pin "2") (pinfunction "2_2") (pintype "passive"))
    )
    (net (code "33") (name "Net-(IC4-CLK)") (class "Default")
      (node (ref "IC4") (pin "20") (pinfunction "CLK_20") (pintype "bidirectional"))
      (node (ref "JP2") (pin "5") (pinfunction "5_5") (pintype "passive"))
    )
    (net (code "34") (name "Net-(IC4-CND)") (class "Default")
      (node (ref "IC4") (pin "19") (pinfunction "CND_19") (pintype "bidirectional"))
      (node (ref "JP2") (pin "6") (pinfunction "6_6") (pintype "passive"))
    )
    (net (code "35") (name "Net-(IC4-IO5)") (class "Default")
      (node (ref "IC4") (pin "29") (pinfunction "IO5_29") (pintype "bidirectional"))
      (node (ref "JP1") (pin "10") (pinfunction "10_10") (pintype "passive"))
      (node (ref "SJ6") (pin "1") (pinfunction "1_1") (pintype "passive"))
    )
    (net (code "36") (name "Net-(IC4-IO17)") (class "Default")
      (node (ref "IC4") (pin "28") (pinfunction "IO17_28") (pintype "bidirectional"))
      (node (ref "JP1") (pin "11") (pinfunction "11_11") (pintype "passive"))
      (node (ref "SJ7") (pin "1") (pinfunction "1_1") (pintype "passive"))
    )
    (net (code "37") (name "Net-(IC4-IO18)") (class "Default")
      (node (ref "IC4") (pin "30") (pinfunction "IO18_30") (pintype "bidirectional"))
      (node (ref "JP1") (pin "9") (pinfunction "9_9") (pintype "passive"))
      (node (ref "SJ5") (pin "1") (pinfunction "1_1") (pintype "passive"))
    )
    (net (code "38") (name "Net-(IC4-IO19)") (class "Default")
      (node (ref "IC4") (pin "31") (pinfunction "IO19_31") (pintype "bidirectional"))
      (node (ref "JP1") (pin "8") (pinfunction "8_8") (pintype "passive"))
      (node (ref "SJ4") (pin "1") (pinfunction "1_1") (pintype "passive"))
    )
    (net (code "39") (name "Net-(IC4-IO20)") (class "Default")
      (node (ref "IC4") (pin "32") (pinfunction "IO20_32") (pintype "bidirectional"))
      (node (ref "JP1") (pin "7") (pinfunction "7_7") (pintype "passive"))
    )
    (net (code "40") (name "Net-(IC4-IO21)") (class "Default")
      (node (ref "IC4") (pin "33") (pinfunction "IO21_33") (pintype "bidirectional"))
      (node (ref "JP1") (pin "6") (pinfunction "6_6") (pintype "passive"))
      (node (ref "SJ2") (pin "1") (pinfunction "1_1") (pintype "passive"))
    )
    (net (code "41") (name "Net-(IC4-IO22)") (class "Default")
      (node (ref "IC4") (pin "36") (pinfunction "IO22_36") (pintype "bidirectional"))
      (node (ref "JP1") (pin "3") (pinfunction "3_3") (pintype "passive"))
      (node (ref "SJ1") (pin "1") (pinfunction "1_1") (pintype "passive"))
    )
    (net (code "42") (name "Net-(IC4-IO23)") (class "Default")
      (node (ref "IC4") (pin "37") (pinfunction "IO23_37") (pintype "bidirectional"))
      (node (ref "JP1") (pin "2") (pinfunction "2_2") (pintype "passive"))
      (node (ref "SJ3") (pin "1") (pinfunction "1_1") (pintype "passive"))
    )
    (net (code "43") (name "Net-(IC4-IO25)") (class "Default")
      (node (ref "IC4") (pin "10") (pinfunction "IO25_10") (pintype "bidirectional"))
      (node (ref "JP3") (pin "5") (pinfunction "5_5") (pintype "passive"))
      (node (ref "SJ11") (pin "2") (pinfunction "2_2") (pintype "passive"))
    )
    (net (code "44") (name "Net-(IC4-IO26)") (class "Default")
      (node (ref "IC4") (pin "11") (pinfunction "IO26_11") (pintype "bidirectional"))
      (node (ref "JP3") (pin "4") (pinfunction "4_4") (pintype "passive"))
      (node (ref "SJ12") (pin "2") (pinfunction "2_2") (pintype "passive"))
    )
    (net (code "45") (name "Net-(IC4-IO27)") (class "Default")
      (node (ref "IC4") (pin "12") (pinfunction "IO27_12") (pintype "bidirectional"))
      (node (ref "JP3") (pin "3") (pinfunction "3_3") (pintype "passive"))
      (node (ref "SJ13") (pin "2") (pinfunction "2_2") (pintype "passive"))
    )
    (net (code "46") (name "Net-(IC4-IO32)") (class "Default")
      (node (ref "IC4") (pin "8") (pinfunction "IO32_8") (pintype "bidirectional"))
      (node (ref "JP3") (pin "7") (pinfunction "7_7") (pintype "passive"))
      (node (ref "SJ9") (pin "2") (pinfunction "2_2") (pintype "passive"))
    )
    (net (code "47") (name "Net-(IC4-IO33)") (class "Default")
      (node (ref "IC4") (pin "9") (pinfunction "IO33_9") (pintype "bidirectional"))
      (node (ref "JP3") (pin "6") (pinfunction "6_6") (pintype "passive"))
      (node (ref "SJ10") (pin "2") (pinfunction "2_2") (pintype "passive"))
    )
    (net (code "48") (name "Net-(IC4-IO34)") (class "Default")
      (node (ref "IC4") (pin "6") (pinfunction "IO34_6") (pintype "bidirectional"))
      (node (ref "JP3") (pin "9") (pinfunction "9_9") (pintype "passive"))
    )
    (net (code "49") (name "Net-(IC4-IO35)") (class "Default")
      (node (ref "IC4") (pin "7") (pinfunction "IO35_7") (pintype "bidirectional"))
      (node (ref "JP3") (pin "8") (pinfunction "8_8") (pintype "passive"))
      (node (ref "SJ8") (pin "2") (pinfunction "2_2") (pintype "passive"))
    )
    (net (code "50") (name "Net-(IC4-SD0)") (class "Default")
      (node (ref "IC4") (pin "21") (pinfunction "SD0_21") (pintype "bidirectional"))
      (node (ref "JP2") (pin "4") (pinfunction "4_4") (pintype "passive"))
    )
    (net (code "51") (name "Net-(IC4-SD1)") (class "Default")
      (node (ref "IC4") (pin "22") (pinfunction "SD1_22") (pintype "bidirectional"))
      (node (ref "JP2") (pin "3") (pinfunction "3_3") (pintype "passive"))
    )
    (net (code "52") (name "Net-(IC4-SD2)") (class "Default")
      (node (ref "IC4") (pin "17") (pinfunction "SD2_17") (pintype "bidirectional"))
      (node (ref "JP2") (pin "8") (pinfunction "8_8") (pintype "passive"))
    )
    (net (code "53") (name "Net-(IC4-SD3)") (class "Default")
      (node (ref "IC4") (pin "18") (pinfunction "SD3_18") (pintype "bidirectional"))
      (node (ref "JP2") (pin "7") (pinfunction "7_7") (pintype "passive"))
    )
    (net (code "54") (name "Net-(IC4-SENSOR_VN)") (class "Default")
      (node (ref "C21") (pin "2") (pinfunction "2_2") (pintype "passive"))
      (node (ref "IC4") (pin "5") (pinfunction "SENSOR_VN_5") (pintype "bidirectional"))
      (node (ref "JP3") (pin "10") (pinfunction "10_10") (pintype "passive"))
    )
    (net (code "55") (name "Net-(IC4-SENSOR_VP)") (class "Default")
      (node (ref "C20") (pin "2") (pinfunction "2_2") (pintype "passive"))
      (node (ref "IC4") (pin "4") (pinfunction "SENSOR_VP_4") (pintype "bidirectional"))
      (node (ref "JP3") (pin "11") (pinfunction "11_11") (pintype "passive"))
    )
    (net (code "56") (name "Net-(Q1-B)") (class "Default")
      (node (ref "Q1") (pin "1") (pinfunction "B_1") (pintype "passive"))
      (node (ref "R6") (pin "2") (pinfunction "2_2") (pintype "passive"))
    )
    (net (code "57") (name "Net-(Q2-B)") (class "Default")
      (node (ref "Q2") (pin "1") (pinfunction "B_1") (pintype "passive"))
      (node (ref "R5") (pin "2") (pinfunction "2_2") (pintype "passive"))
    )
    (net (code "58") (name "Net-(Q3-D)") (class "Default")
      (node (ref "C14") (pin "2") (pinfunction "2_2") (pintype "passive"))
      (node (ref "D7") (pin "A") (pinfunction "A_A") (pintype "passive"))
      (node (ref "L1") (pin "2") (pinfunction "2_2") (pintype "passive"))
      (node (ref "Q3") (pin "3") (pinfunction "D_3") (pintype "passive"))
    )
    (net (code "59") (name "PREVGH") (class "Default")
      (node (ref "C13") (pin "2") (pinfunction "2_2") (pintype "passive"))
      (node (ref "D7") (pin "C") (pinfunction "C_C") (pintype "passive"))
      (node (ref "J1") (pin "4") (pinfunction "4_4") (pintype "passive"))
    )
    (net (code "60") (name "PREVGL") (class "Default")
      (node (ref "C9") (pin "2") (pinfunction "2_2") (pintype "passive"))
      (node (ref "D2") (pin "A") (pinfunction "A_A") (pintype "passive"))
      (node (ref "J1") (pin "2") (pinfunction "2_2") (pintype "passive"))
    )
    (net (code "61") (name "RESE") (class "Default")
      (node (ref "J1") (pin "22") (pinfunction "22_22") (pintype "passive"))
      (node (ref "Q3") (pin "2") (pinfunction "S_2") (pintype "passive"))
      (node (ref "R7") (pin "1") (pinfunction "1_1") (pintype "passive"))
    )
    (net (code "62") (name "SD_CD") (class "Default")
      (node (ref "IC4") (pin "27") (pinfunction "IO16_27") (pintype "bidirectional"))
      (node (ref "JP1") (pin "12") (pinfunction "12_12") (pintype "passive"))
      (node (ref "R10") (pin "2") (pinfunction "2_2") (pintype "passive"))
      (node (ref "X701") (pin "CD1") (pinfunction "SHIELD_CD1") (pintype "bidirectional"))
    )
    (net (code "63") (name "SD_CLK") (class "Default")
      (node (ref "IC4") (pin "13") (pinfunction "IO14_13") (pintype "bidirectional"))
      (node (ref "JP3") (pin "2") (pinfunction "2_2") (pintype "passive"))
      (node (ref "X701") (pin "5") (pinfunction "SCK_5") (pintype "bidirectional"))
    )
    (net (code "64") (name "SD_CMD") (class "Default")
      (node (ref "IC4") (pin "23") (pinfunction "IO15_23") (pintype "bidirectional"))
      (node (ref "JP2") (pin "2") (pinfunction "2_2") (pintype "passive"))
      (node (ref "X701") (pin "3") (pinfunction "DI_3") (pintype "bidirectional"))
    )
    (net (code "65") (name "SD_DATA0") (class "Default")
      (node (ref "IC4") (pin "24") (pinfunction "IO2_24") (pintype "bidirectional"))
      (node (ref "JP2") (pin "1") (pinfunction "1_1") (pintype "passive"))
      (node (ref "X701") (pin "7") (pinfunction "DO_7") (pintype "bidirectional"))
    )
    (net (code "66") (name "SD_DATA1") (class "Default")
      (node (ref "IC4") (pin "26") (pinfunction "IO4_26") (pintype "bidirectional"))
      (node (ref "JP1") (pin "13") (pinfunction "13_13") (pintype "passive"))
      (node (ref "X701") (pin "8") (pinfunction "RSV_8") (pintype "bidirectional"))
    )
    (net (code "67") (name "SD_DATA2") (class "Default")
      (node (ref "IC4") (pin "14") (pinfunction "IO12_14") (pintype "bidirectional"))
      (node (ref "JP3") (pin "1") (pinfunction "1_1") (pintype "passive"))
      (node (ref "X701") (pin "1") (pinfunction "NC_1") (pintype "bidirectional"))
    )
    (net (code "68") (name "SD_DATA3") (class "Default")
      (node (ref "IC4") (pin "16") (pinfunction "IO13_16") (pintype "bidirectional"))
      (node (ref "JP2") (pin "9") (pinfunction "9_9") (pintype "passive"))
      (node (ref "X701") (pin "2") (pinfunction "CS_2") (pintype "bidirectional"))
    )
    (net (code "69") (name "TSCL") (class "Default")
      (node (ref "J1") (pin "19") (pinfunction "19_19") (pintype "passive"))
    )
    (net (code "70") (name "TSDA") (class "Default")
      (node (ref "J1") (pin "18") (pinfunction "18_18") (pintype "passive"))
    )
    (net (code "71") (name "VCOM") (class "Default")
      (node (ref "C7") (pin "2") (pinfunction "2_2") (pintype "passive"))
      (node (ref "J1") (pin "1") (pinfunction "1_1") (pintype "passive"))
    )
    (net (code "72") (name "VDD") (class "Default")
      (node (ref "C6") (pin "1") (pinfunction "1_1") (pintype "passive"))
      (node (ref "IC3") (pin "6") (pinfunction "VDD_6") (pintype "power_in"))
      (node (ref "R1") (pin "2") (pinfunction "2_2") (pintype "passive"))
      (node (ref "R2") (pin "2") (pinfunction "2_2") (pintype "passive"))
      (node (ref "R3") (pin "1") (pinfunction "1_1") (pintype "passive"))
      (node (ref "R4") (pin "2") (pinfunction "2_2") (pintype "passive"))
    )
    (net (code "73") (name "VGH") (class "Default")
      (node (ref "C17") (pin "2") (pinfunction "2_2") (pintype "passive"))
      (node (ref "J1") (pin "20") (pinfunction "20_20") (pintype "passive"))
    )
    (net (code "74") (name "VGL") (class "Default")
      (node (ref "C18") (pin "2") (pinfunction "2_2") (pintype "passive"))
      (node (ref "J1") (pin "21") (pinfunction "21_21") (pintype "passive"))
    )
    (net (code "75") (name "VPP") (class "Default")
      (node (ref "J1") (pin "6") (pinfunction "6_6") (pintype "passive"))
    )
    (net (code "76") (name "VSH") (class "Default")
      (node (ref "C12") (pin "2") (pinfunction "2_2") (pintype "passive"))
      (node (ref "J1") (pin "5") (pinfunction "5_5") (pintype "passive"))
    )
    (net (code "77") (name "VSL") (class "Default")
      (node (ref "C10") (pin "2") (pinfunction "2_2") (pintype "passive"))
      (node (ref "J1") (pin "3") (pinfunction "3_3") (pintype "passive"))
    )
    (net (code "78") (name "unconnected-(IC3-CTS-Pad23)") (class "Default")
      (node (ref "IC3") (pin "23") (pinfunction "CTS_23") (pintype "input"))
    )
    (net (code "79") (name "unconnected-(IC3-DCD-Pad1)") (class "Default")
      (node (ref "IC3") (pin "1") (pinfunction "DCD_1") (pintype "input"))
    )
    (net (code "80") (name "unconnected-(IC3-DSR-Pad27)") (class "Default")
      (node (ref "IC3") (pin "27") (pinfunction "DSR_27") (pintype "input"))
    )
    (net (code "81") (name "unconnected-(IC3-RI-Pad2)") (class "Default")
      (node (ref "IC3") (pin "2") (pinfunction "RI_2") (pintype "input"))
    )
    (net (code "82") (name "unconnected-(IC3-SUSPEND-Pad12)") (class "Default")
      (node (ref "IC3") (pin "12") (pinfunction "SUSPEND_12") (pintype "output"))
    )
    (net (code "83") (name "unconnected-(IC3-~{SUSPEND}-Pad11)") (class "Default")
      (node (ref "IC3") (pin "11") (pinfunction "~{SUSPEND}_11") (pintype "output"))
    )
    (net (code "84") (name "unconnected-(J1-Pad24)") (class "Default")
      (node (ref "J1") (pin "24") (pinfunction "24_24") (pintype "passive"))
    )
    (net (code "85") (name "unconnected-(USB1-Pad4)") (class "Default")
      (node (ref "USB1") (pin "4") (pinfunction "4_4") (pintype "input"))
    )
  )
)
